# CAN-FD.net
KiCad netlist of a schematic drawn in Altium Designer
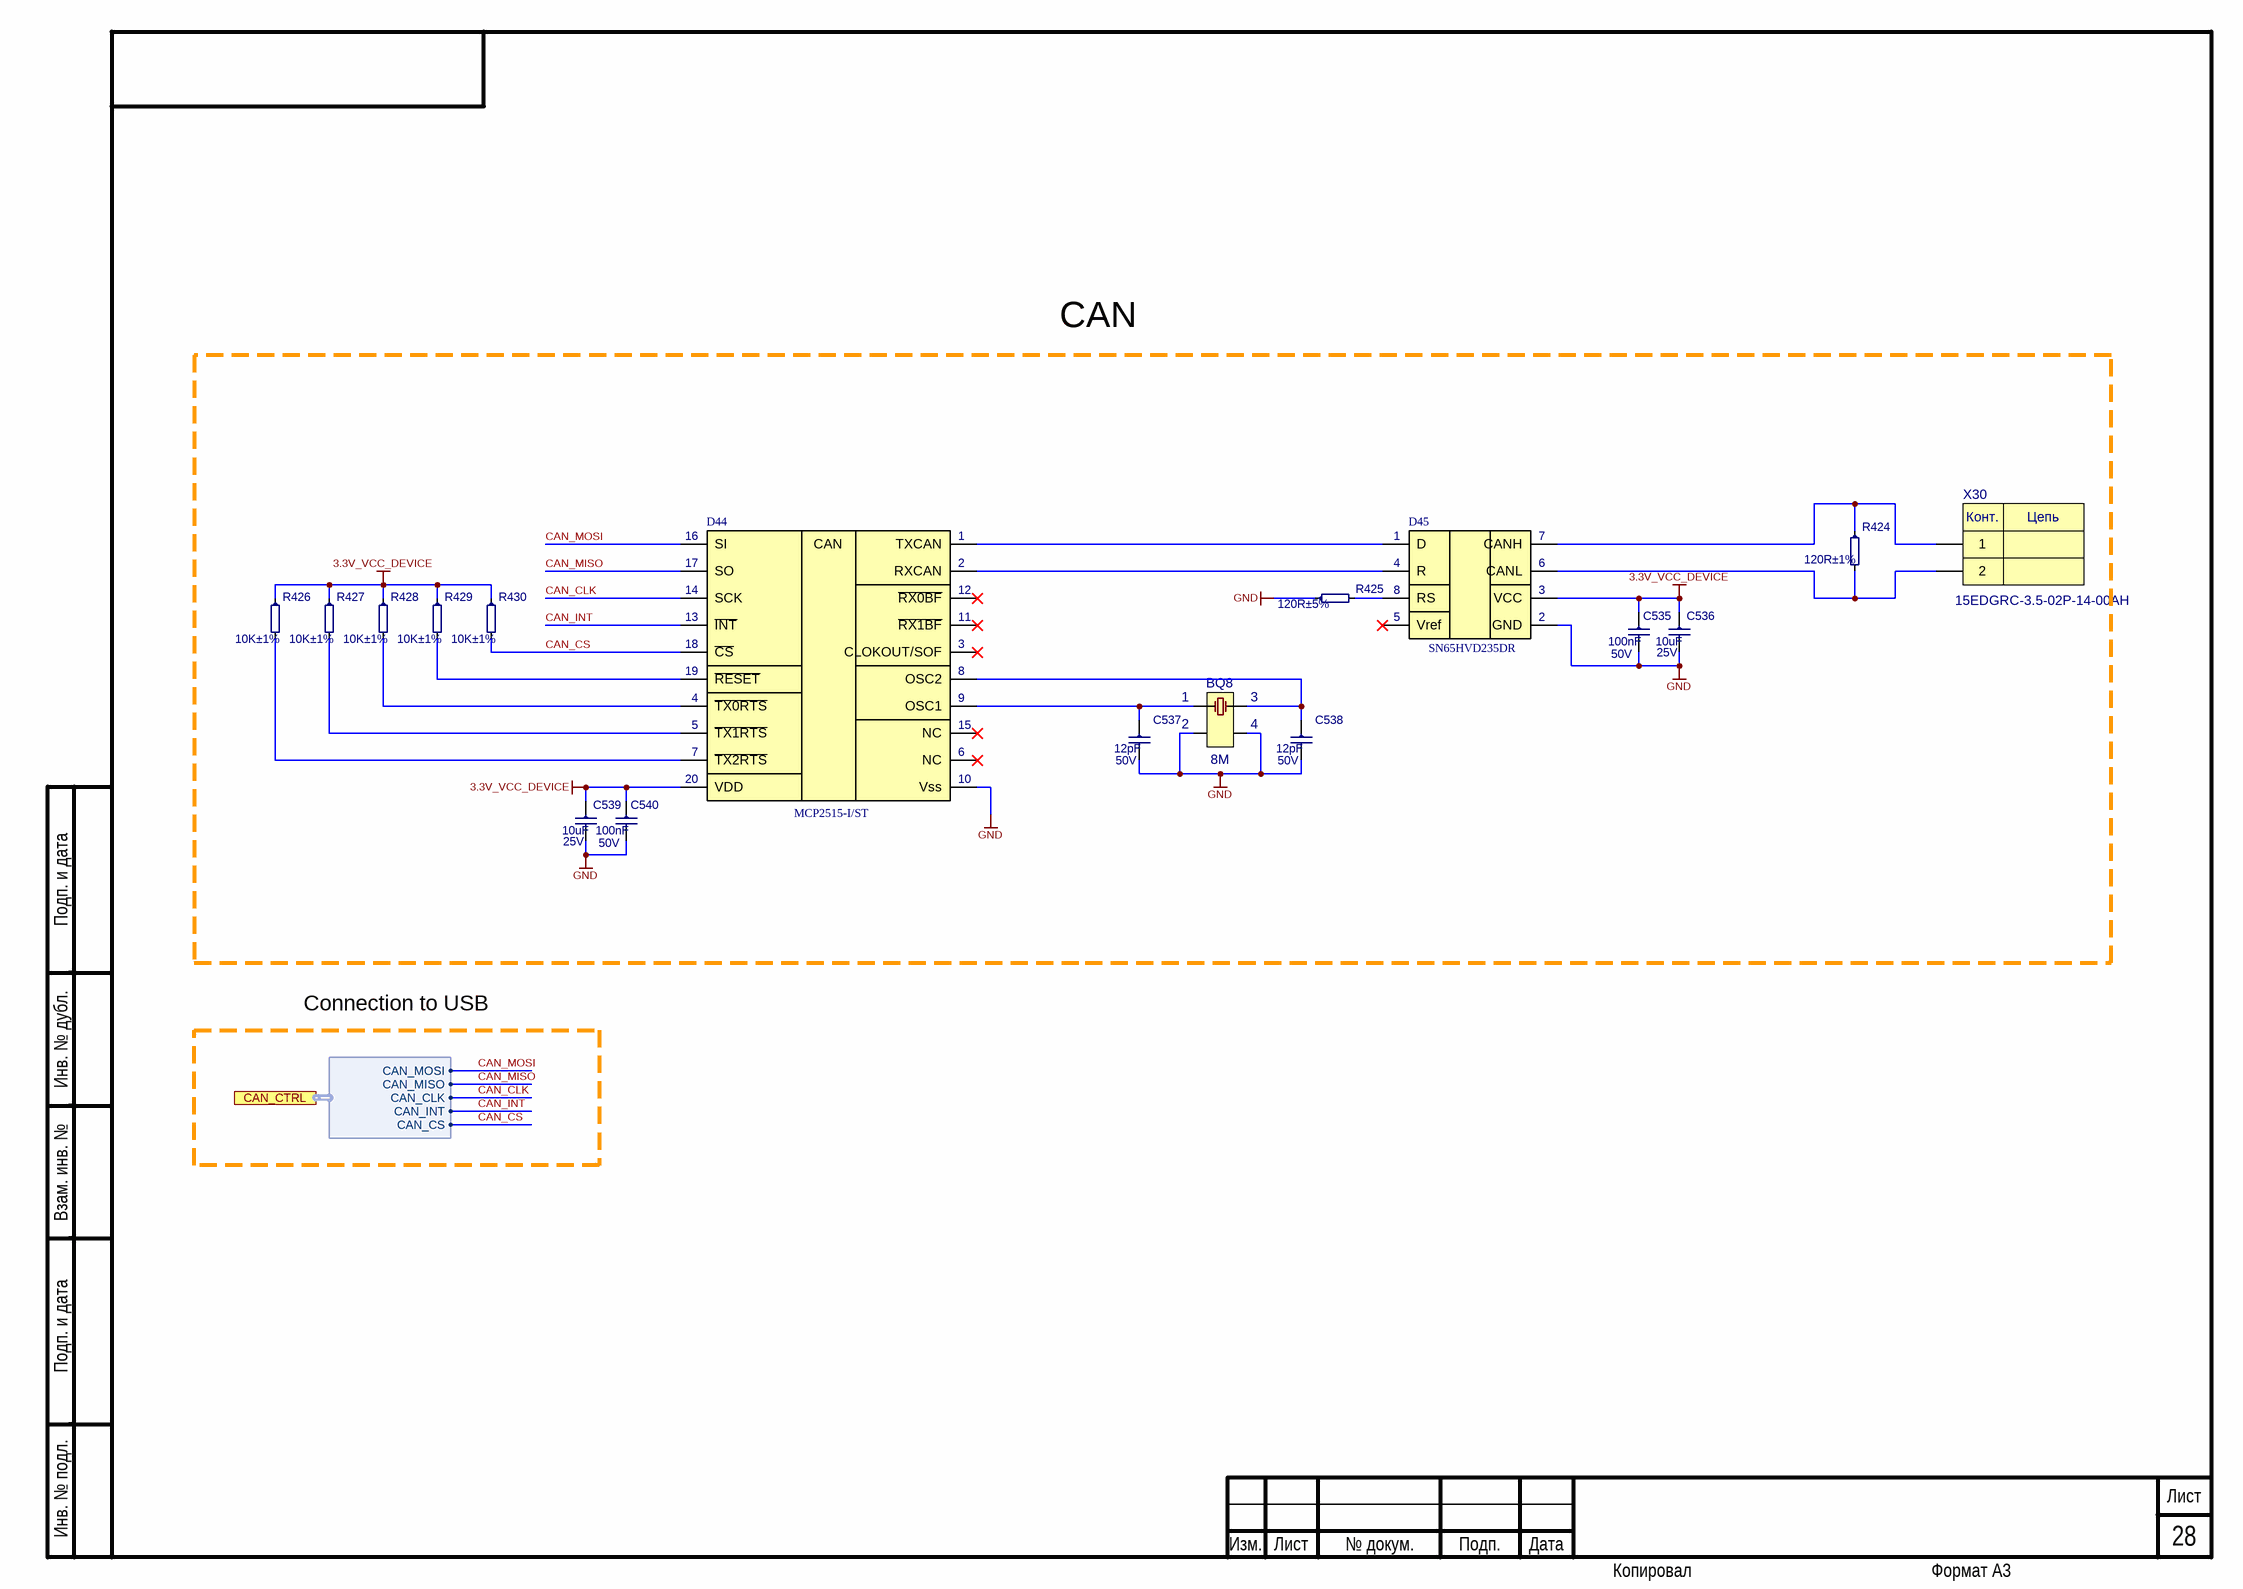
[diagram p0: CAN-FD.SchDoc]

(export (version "E")
  (design (tool "Eeschema 10.0.6"))
  (components
    (comp (ref "BQ8")
      (value "8M")
      (footprint "NX3225GA")
      (description "8MHz 3225 quartz 4 pin")
      (fields (field (name "PART NUMBER") "X32258MOB4SI") (field (name "TOLERANCE") "20ppm"))
      (libsource (lib "ATB") (part "BQ_4pin_2closed_2.4_2.4"))
    )
    (comp (ref "C535")
      (value "100nF")
      (footprint "C0402")
      (description "Ceramic Capacitor 0402 100nF ±10% 50V X7R")
      (fields
        (field (name "VOLTAGE") "50V")
        (field (name "PART NUMBER") "0402-X7R-50V-0.1uF±10%")
        (field (name "TOLERANCE") "10%")
      )
      (libsource (lib "ATB") (part "C"))
    )
    (comp (ref "C536")
      (value "10uF")
      (footprint "C0805")
      (fields
        (field (name "VOLTAGE") "25V")
        (field (name "PART NUMBER") "0805-X5R-25V-10uF±10%")
        (field (name "TOLERANCE") "10%")
        (field (name "MANUFACTURER") "Samsung")
      )
      (libsource (lib "ATB") (part "C"))
    )
    (comp (ref "C537")
      (value "12pF")
      (footprint "C0402")
      (fields
        (field (name "VOLTAGE") "50V")
        (field (name "PART NUMBER") "0402-NP0-50V-12pF±5%")
        (field (name "TOLERANCE") "5%")
        (field (name "MANUFACTURER") "Murata Electronics")
      )
      (libsource (lib "ATB") (part "C"))
    )
    (comp (ref "C538")
      (value "12pF")
      (footprint "C0402")
      (fields
        (field (name "VOLTAGE") "50V")
        (field (name "PART NUMBER") "0402-NP0-50V-12pF±5%")
        (field (name "TOLERANCE") "5%")
        (field (name "MANUFACTURER") "Murata Electronics")
      )
      (libsource (lib "ATB") (part "C"))
    )
    (comp (ref "C539")
      (value "10uF")
      (footprint "C0805")
      (fields
        (field (name "VOLTAGE") "25V")
        (field (name "PART NUMBER") "0805-X5R-25V-10uF±10%")
        (field (name "TOLERANCE") "10%")
        (field (name "MANUFACTURER") "Samsung")
      )
      (libsource (lib "ATB") (part "C"))
    )
    (comp (ref "C540")
      (value "100nF")
      (footprint "C0402")
      (description "Ceramic Capacitor 0402 100nF ±10% 50V X7R")
      (fields
        (field (name "VOLTAGE") "50V")
        (field (name "PART NUMBER") "0402-X7R-50V-0.1uF±10%")
        (field (name "TOLERANCE") "10%")
      )
      (libsource (lib "ATB") (part "C"))
    )
    (comp (ref "D44")
      (value "MCP2515-I/ST")
      (footprint "MCP2515-I/ST")
      (description "1Mbps CAN Controller TSSOP-20 Interface Controllers RoHS")
      (fields (field (name "MANUFACTURER") "MICROCHIP"))
      (libsource (lib "LIB_RK") (part "MCP2515-I/ST"))
    )
    (comp (ref "D45")
      (value "SN65HVD235DR")
      (footprint "SN65HVD235DR")
      (description "3V~3.6V CAN Transceiver 1Mbps SOIC-8 Drivers, Receivers, Transceivers RoHS")
      (fields (field (name "MANUFACTURER") "TI"))
      (libsource (lib "LIB_RK") (part "SN65HVD235DR"))
    )
    (comp (ref "R424")
      (value "120R±1%")
      (footprint "R1206")
      (fields
        (field (name "PART NUMBER") "1206-0.25W-120R-100ppm±1%")
        (field (name "TOLERANCE") "1%")
        (field (name "MANUFACTURER") "Yageo")
      )
      (libsource (lib "ATB") (part "R"))
    )
    (comp (ref "R425")
      (value "120R±5%")
      (footprint "R0402")
      (fields
        (field (name "PART NUMBER") "0402-0.0625W-120R-200ppm±5%")
        (field (name "TOLERANCE") "5%")
        (field (name "MANUFACTURER") "Yageo")
      )
      (libsource (lib "ATB") (part "R"))
    )
    (comp (ref "R426")
      (value "10K±1%")
      (footprint "R0402")
      (description "Chip Resistor 0402 10kΩ ±1% 50V ±100ppm/℃ Thick Film")
      (fields (field (name "PART NUMBER") "0402-0.0625W-10K-100ppm±1%") (field (name "TOLERANCE") "1%"))
      (libsource (lib "ATB") (part "R"))
    )
    (comp (ref "R427")
      (value "10K±1%")
      (footprint "R0402")
      (description "Chip Resistor 0402 10kΩ ±1% 50V ±100ppm/℃ Thick Film")
      (fields (field (name "PART NUMBER") "0402-0.0625W-10K-100ppm±1%") (field (name "TOLERANCE") "1%"))
      (libsource (lib "ATB") (part "R"))
    )
    (comp (ref "R428")
      (value "10K±1%")
      (footprint "R0402")
      (description "Chip Resistor 0402 10kΩ ±1% 50V ±100ppm/℃ Thick Film")
      (fields (field (name "PART NUMBER") "0402-0.0625W-10K-100ppm±1%") (field (name "TOLERANCE") "1%"))
      (libsource (lib "ATB") (part "R"))
    )
    (comp (ref "R429")
      (value "10K±1%")
      (footprint "R0402")
      (description "Chip Resistor 0402 10kΩ ±1% 50V ±100ppm/℃ Thick Film")
      (fields (field (name "PART NUMBER") "0402-0.0625W-10K-100ppm±1%") (field (name "TOLERANCE") "1%"))
      (libsource (lib "ATB") (part "R"))
    )
    (comp (ref "R430")
      (value "10K±1%")
      (footprint "R0402")
      (description "Chip Resistor 0402 10kΩ ±1% 50V ±100ppm/℃ Thick Film")
      (fields (field (name "PART NUMBER") "0402-0.0625W-10K-100ppm±1%") (field (name "TOLERANCE") "1%"))
      (libsource (lib "ATB") (part "R"))
    )
    (comp (ref "X30")
      (value "15EDGRC-3.5-02P-14-00AH")
      (footprint "D1RFRD006-02")
      (description "Terminal block 2")
      (fields (field (name "MANUFACTURER") "Degson"))
      (libsource (lib "ATB") (part "H2"))
    )
  )
  (nets
    (net (code "2") (name "/CAN_CLK") (class "Default")
      (node (ref "D44") (pin "14") (pinfunction "SCK_14") (pintype "passive"))
    )
    (net (code "3") (name "/CAN_CS") (class "Default")
      (node (ref "D44") (pin "18") (pinfunction "~{CS}_18") (pintype "passive"))
      (node (ref "R430") (pin "2") (pinfunction "2_2") (pintype "passive"))
    )
    (net (code "4") (name "/CAN_INT") (class "Default")
      (node (ref "D44") (pin "13") (pinfunction "~{INT}_13") (pintype "passive"))
    )
    (net (code "5") (name "/CAN_MISO") (class "Default")
      (node (ref "D44") (pin "17") (pinfunction "SO_17") (pintype "passive"))
    )
    (net (code "6") (name "/CAN_MOSI") (class "Default")
      (node (ref "D44") (pin "16") (pinfunction "SI_16") (pintype "passive"))
    )
    (net (code "8") (name "3.3V_VCC_DEVICE") (class "Default")
      (node (ref "C535") (pin "1") (pinfunction "1_1") (pintype "passive"))
      (node (ref "C536") (pin "1") (pinfunction "1_1") (pintype "passive"))
      (node (ref "C539") (pin "1") (pinfunction "1_1") (pintype "passive"))
      (node (ref "C540") (pin "1") (pinfunction "1_1") (pintype "passive"))
      (node (ref "D44") (pin "20") (pinfunction "VDD_20") (pintype "passive"))
      (node (ref "D45") (pin "3") (pinfunction "VCC_3") (pintype "passive"))
      (node (ref "R426") (pin "1") (pinfunction "1_1") (pintype "passive"))
      (node (ref "R427") (pin "1") (pinfunction "1_1") (pintype "passive"))
      (node (ref "R428") (pin "1") (pinfunction "1_1") (pintype "passive"))
      (node (ref "R429") (pin "1") (pinfunction "1_1") (pintype "passive"))
      (node (ref "R430") (pin "1") (pinfunction "1_1") (pintype "passive"))
    )
    (net (code "9") (name "GND") (class "Default")
      (node (ref "BQ8") (pin "2") (pinfunction "2_2") (pintype "passive"))
      (node (ref "BQ8") (pin "4") (pinfunction "4_4") (pintype "passive"))
      (node (ref "C535") (pin "2") (pinfunction "2_2") (pintype "passive"))
      (node (ref "C536") (pin "2") (pinfunction "2_2") (pintype "passive"))
      (node (ref "C537") (pin "2") (pinfunction "2_2") (pintype "passive"))
      (node (ref "C538") (pin "2") (pinfunction "2_2") (pintype "passive"))
      (node (ref "C539") (pin "2") (pinfunction "2_2") (pintype "passive"))
      (node (ref "C540") (pin "2") (pinfunction "2_2") (pintype "passive"))
      (node (ref "D44") (pin "10") (pinfunction "Vss_10") (pintype "passive"))
      (node (ref "D45") (pin "2") (pinfunction "GND_2") (pintype "passive"))
      (node (ref "R425") (pin "1") (pinfunction "1_1") (pintype "passive"))
    )
    (net (code "10") (name "Net-(D44-OSC1)") (class "Default")
      (node (ref "BQ8") (pin "1") (pinfunction "1_1") (pintype "passive"))
      (node (ref "C537") (pin "1") (pinfunction "1_1") (pintype "passive"))
      (node (ref "D44") (pin "9") (pinfunction "OSC1_9") (pintype "passive"))
    )
    (net (code "11") (name "Net-(D44-OSC2)") (class "Default")
      (node (ref "BQ8") (pin "3") (pinfunction "3_3") (pintype "passive"))
      (node (ref "C538") (pin "1") (pinfunction "1_1") (pintype "passive"))
      (node (ref "D44") (pin "8") (pinfunction "OSC2_8") (pintype "passive"))
    )
    (net (code "12") (name "Net-(D44-RXCAN)") (class "Default")
      (node (ref "D44") (pin "2") (pinfunction "RXCAN_2") (pintype "passive"))
      (node (ref "D45") (pin "4") (pinfunction "R_4") (pintype "passive"))
    )
    (net (code "13") (name "Net-(D44-TXCAN)") (class "Default")
      (node (ref "D44") (pin "1") (pinfunction "TXCAN_1") (pintype "passive"))
      (node (ref "D45") (pin "1") (pinfunction "D_1") (pintype "passive"))
    )
    (net (code "14") (name "Net-(D44-~{RESET})") (class "Default")
      (node (ref "D44") (pin "19") (pinfunction "~{RESET}_19") (pintype "passive"))
      (node (ref "R429") (pin "2") (pinfunction "2_2") (pintype "passive"))
    )
    (net (code "15") (name "Net-(D44-~{TX0RTS})") (class "Default")
      (node (ref "D44") (pin "4") (pinfunction "~{TX0RTS}_4") (pintype "passive"))
      (node (ref "R428") (pin "2") (pinfunction "2_2") (pintype "passive"))
    )
    (net (code "16") (name "Net-(D44-~{TX1RTS})") (class "Default")
      (node (ref "D44") (pin "5") (pinfunction "~{TX1RTS}_5") (pintype "passive"))
      (node (ref "R427") (pin "2") (pinfunction "2_2") (pintype "passive"))
    )
    (net (code "17") (name "Net-(D44-~{TX2RTS})") (class "Default")
      (node (ref "D44") (pin "7") (pinfunction "~{TX2RTS}_7") (pintype "passive"))
      (node (ref "R426") (pin "2") (pinfunction "2_2") (pintype "passive"))
    )
    (net (code "18") (name "Net-(D45-CANH)") (class "Default")
      (node (ref "D45") (pin "7") (pinfunction "CANH_7") (pintype "passive"))
      (node (ref "R424") (pin "1") (pinfunction "1_1") (pintype "passive"))
      (node (ref "X30") (pin "1") (pinfunction "1_1") (pintype "passive"))
    )
    (net (code "19") (name "Net-(D45-CANL)") (class "Default")
      (node (ref "D45") (pin "6") (pinfunction "CANL_6") (pintype "passive"))
      (node (ref "R424") (pin "2") (pinfunction "2_2") (pintype "passive"))
      (node (ref "X30") (pin "2") (pinfunction "2_2") (pintype "passive"))
    )
    (net (code "20") (name "Net-(D45-RS)") (class "Default")
      (node (ref "D45") (pin "8") (pinfunction "RS_8") (pintype "passive"))
      (node (ref "R425") (pin "2") (pinfunction "2_2") (pintype "passive"))
    )
    (net (code "21") (name "unconnected-(D44-CLOKOUT{slash}SOF-Pad3)") (class "Default")
      (node (ref "D44") (pin "3") (pinfunction "CLOKOUT/SOF_3") (pintype "passive+no_connect"))
    )
    (net (code "22") (name "unconnected-(D44-NC-Pad6)") (class "Default")
      (node (ref "D44") (pin "6") (pinfunction "NC_6") (pintype "passive+no_connect"))
    )
    (net (code "23") (name "unconnected-(D44-NC-Pad15)") (class "Default")
      (node (ref "D44") (pin "15") (pinfunction "NC_15") (pintype "passive+no_connect"))
    )
    (net (code "24") (name "unconnected-(D44-~{RX0BF}-Pad12)") (class "Default")
      (node (ref "D44") (pin "12") (pinfunction "~{RX0BF}_12") (pintype "passive+no_connect"))
    )
    (net (code "25") (name "unconnected-(D44-~{RX1BF}-Pad11)") (class "Default")
      (node (ref "D44") (pin "11") (pinfunction "~{RX1BF}_11") (pintype "passive+no_connect"))
    )
    (net (code "26") (name "unconnected-(D45-Vref-Pad5)") (class "Default")
      (node (ref "D45") (pin "5") (pinfunction "Vref_5") (pintype "passive+no_connect"))
    )
  )
)
